# Photodiode_Sun_Sensor.net
KiCad netlist of a schematic drawn in Altium Designer
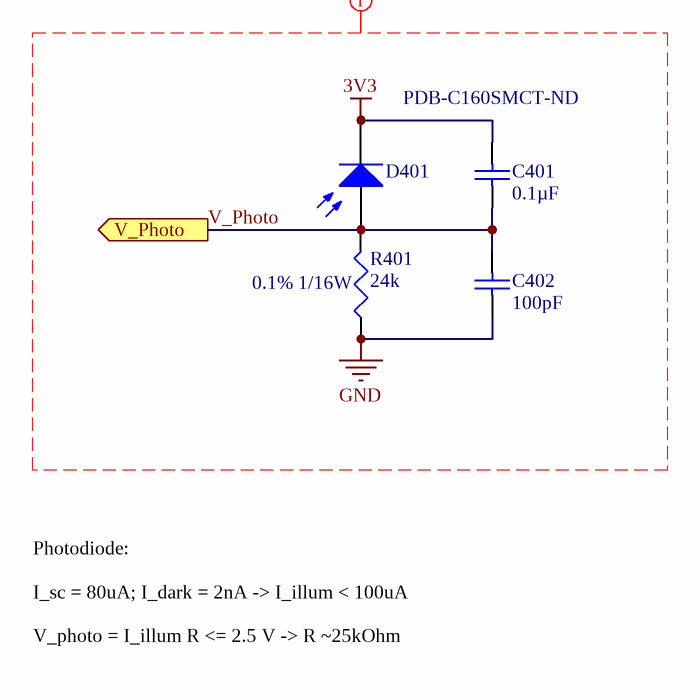
[diagram p0: Photodiode_Sun_Sensor.SchDoc]

(export (version "E")
  (design (tool "Eeschema 10.0.6"))
  (components
    (comp (ref "C401")
      (value "0.1µF")
      (footprint "TDK-CGA2B")
      (description "CAP CER 0.1UF 50V X7R 0402")
      (fields
        (field (name "PART NUMBER") "PC-TDK-02259")
        (field (name "MANUFACTURER PART NUMBER") "CGA2B3X7R1H104K050BB")
        (field (name "PUBLISHER") "AlbertaSat")
      )
      (libsource (lib "Database") (part "Cap"))
    )
    (comp (ref "C402")
      (value "100pF")
      (footprint "TDK-CGA2B")
      (description "CAP CER 100PF 50V C0G 0402")
      (fields
        (field (name "PART NUMBER") "PC-TDK-01227")
        (field (name "MANUFACTURER PART NUMBER") "CGA2B2C0G1H101J050BA")
        (field (name "PUBLISHER") "AlbertaSat")
      )
      (libsource (lib "Database") (part "Cap"))
    )
    (comp (ref "D401")
      (value "PDB-C160SMCT-ND")
      (footprint "PDB-C160SM")
      (description "SENSOR PHOTODIODE 850NM 2SMD GW")
      (fields
        (field (name "PART NUMBER") "PXX-ADP-00000")
        (field (name "MANUFACTURER PART NUMBER") "Advanced Photonics")
        (field (name "PUBLISHER") "AlbertaSat")
      )
      (libsource (lib "Database") (part "Photo Sen"))
    )
    (comp (ref "R401")
      (value "0.1% 1/16W")
      (footprint "PANA-ERA2A")
      (description "RES SMD 24K OHM 0.1% 1/16W 0402")
      (fields
        (field (name "ALTIUM_VALUE") "24k")
        (field (name "PART NUMBER") "17830")
        (field (name "MANUFACTURER PART NUMBER") "ERA-2APB243X")
        (field (name "PUBLISHER") "Altium Limited")
      )
      (libsource (lib "Database") (part "Res3"))
    )
  )
  (nets
    (net (code "1") (name "/V_Photo") (class "Default")
      (node (ref "C401") (pin "1") (pinfunction "1_1") (pintype "passive"))
      (node (ref "C402") (pin "2") (pinfunction "2_2") (pintype "passive"))
      (node (ref "D401") (pin "1") (pinfunction "A_1") (pintype "passive"))
      (node (ref "R401") (pin "2") (pinfunction "2_2") (pintype "passive"))
    )
    (net (code "2") (name "3V3") (class "Default")
      (node (ref "C401") (pin "2") (pinfunction "2_2") (pintype "passive"))
      (node (ref "D401") (pin "2") (pinfunction "K_2") (pintype "passive"))
    )
    (net (code "3") (name "GND") (class "Default")
      (node (ref "C402") (pin "1") (pinfunction "1_1") (pintype "passive"))
      (node (ref "R401") (pin "1") (pinfunction "1_1") (pintype "passive"))
    )
  )
)
